# atom-hub-proto-example.net
KiCad netlist of a schematic drawn in EAGLE
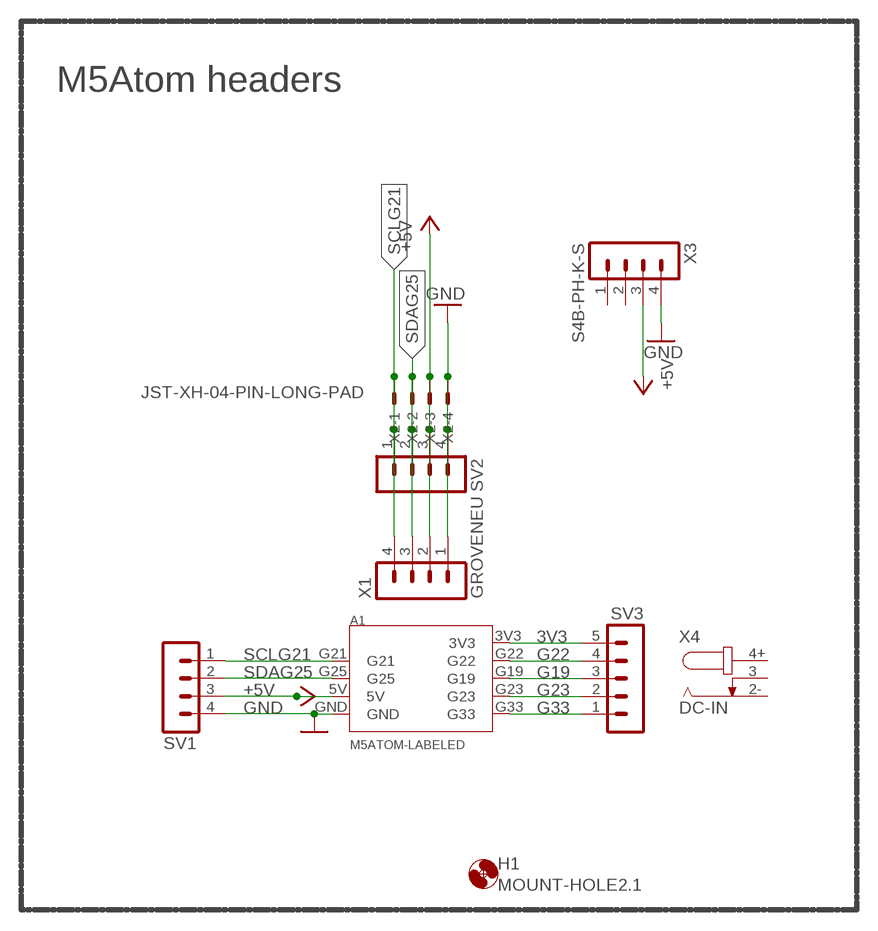
[diagram p0: schematic, sheet 1]

(export (version "E")
  (design (tool "Eeschema 10.0.6"))
  (components
    (comp (ref "A1")
      (value "M5ATOM-LABELED")
      (footprint "eagle-import:M5ATOM-W_-LABELS")
      (libsource (lib "eagle-import") (part "M5ATOM-LABELED"))
    )
    (comp (ref "H1")
      (value "MOUNT-HOLE2.1")
      (footprint "eagle-import:2,1")
      (libsource (lib "eagle-import") (part "MOUNT-HOLE2.1"))
    )
    (comp (ref "SV1")
      (value "MA04-1")
      (footprint "eagle-import:MA04-1")
      (libsource (lib "eagle-import") (part "MA04-1"))
    )
    (comp (ref "SV2")
      (value "MA04-1")
      (footprint "eagle-import:MA04-1")
      (libsource (lib "eagle-import") (part "MA04-1"))
    )
    (comp (ref "SV3")
      (value "MA05-1")
      (footprint "eagle-import:MA05-1")
      (libsource (lib "eagle-import") (part "MA05-1"))
    )
    (comp (ref "X1")
      (value "GROVENEU")
      (footprint "eagle-import:GROVE-NEU")
      (libsource (lib "eagle-import") (part "GROVENEU"))
    )
    (comp (ref "X2")
      (value "JST-XH-04-PIN-LONG-PAD")
      (footprint "eagle-import:JST-XH-04-PACKAGE-LONG-PAD")
      (libsource (lib "eagle-import") (part "JST-XH-04-PIN-LONG-PAD"))
    )
    (comp (ref "X3")
      (value "S4B-PH-K-S")
      (footprint "eagle-import:S4B-PH-K-S")
      (libsource (lib "eagle-import") (part "S4B-PH-K-S"))
    )
    (comp (ref "X4")
      (value "DC-IN")
      (footprint "eagle-import:DC-IN-TH_DC-0440-2.5A-2.0")
      (libsource (lib "eagle-import") (part "DC-IN"))
    )
  )
  (nets
    (net (code "1") (name "+5V") (class "Default")
      (node (ref "A1") (pin "5V") (pinfunction "5V_5V") (pintype "bidirectional"))
      (node (ref "SV1") (pin "3") (pinfunction "3_3") (pintype "passive"))
      (node (ref "SV2") (pin "3") (pinfunction "3_3") (pintype "passive"))
      (node (ref "X1") (pin "2") (pinfunction "2_2") (pintype "passive"))
      (node (ref "X2") (pin "3") (pinfunction "S_3") (pintype "passive"))
      (node (ref "X3") (pin "3") (pinfunction "3_3") (pintype "passive"))
    )
    (net (code "2") (name "/3V3") (class "Default")
      (node (ref "A1") (pin "3V3") (pinfunction "3V3_3V3") (pintype "bidirectional"))
      (node (ref "SV3") (pin "5") (pinfunction "5_5") (pintype "passive"))
    )
    (net (code "3") (name "/G19") (class "Default")
      (node (ref "A1") (pin "G19") (pinfunction "G19_G19") (pintype "bidirectional"))
      (node (ref "SV3") (pin "3") (pinfunction "3_3") (pintype "passive"))
    )
    (net (code "4") (name "/G22") (class "Default")
      (node (ref "A1") (pin "G22") (pinfunction "G22_G22") (pintype "bidirectional"))
      (node (ref "SV3") (pin "4") (pinfunction "4_4") (pintype "passive"))
    )
    (net (code "5") (name "/G23") (class "Default")
      (node (ref "A1") (pin "G23") (pinfunction "G23_G23") (pintype "bidirectional"))
      (node (ref "SV3") (pin "2") (pinfunction "2_2") (pintype "passive"))
    )
    (net (code "6") (name "/G33") (class "Default")
      (node (ref "A1") (pin "G33") (pinfunction "G33_G33") (pintype "bidirectional"))
      (node (ref "SV3") (pin "1") (pinfunction "1_1") (pintype "passive"))
    )
    (net (code "7") (name "GND") (class "Default")
      (node (ref "A1") (pin "GND") (pinfunction "GND_GND") (pintype "bidirectional"))
      (node (ref "SV1") (pin "4") (pinfunction "4_4") (pintype "passive"))
      (node (ref "SV2") (pin "4") (pinfunction "4_4") (pintype "passive"))
      (node (ref "X1") (pin "1") (pinfunction "1_1") (pintype "passive"))
      (node (ref "X2") (pin "4") (pinfunction "S_4") (pintype "passive"))
      (node (ref "X3") (pin "4") (pinfunction "4_4") (pintype "passive"))
    )
    (net (code "8") (name "SCLG21") (class "Default")
      (node (ref "A1") (pin "G21") (pinfunction "G21_G21") (pintype "bidirectional"))
      (node (ref "SV1") (pin "1") (pinfunction "1_1") (pintype "passive"))
      (node (ref "SV2") (pin "1") (pinfunction "1_1") (pintype "passive"))
      (node (ref "X1") (pin "4") (pinfunction "4_4") (pintype "passive"))
      (node (ref "X2") (pin "1") (pinfunction "S_1") (pintype "passive"))
    )
    (net (code "9") (name "SDAG25") (class "Default")
      (node (ref "A1") (pin "G25") (pinfunction "G25_G25") (pintype "bidirectional"))
      (node (ref "SV1") (pin "2") (pinfunction "2_2") (pintype "passive"))
      (node (ref "SV2") (pin "2") (pinfunction "2_2") (pintype "passive"))
      (node (ref "X1") (pin "3") (pinfunction "3_3") (pintype "passive"))
      (node (ref "X2") (pin "2") (pinfunction "S_2") (pintype "passive"))
    )
    (net (code "10") (name "unconnected-(X3-Pad1)") (class "Default")
      (node (ref "X3") (pin "1") (pinfunction "1_1") (pintype "passive"))
    )
    (net (code "11") (name "unconnected-(X3-Pad2)") (class "Default")
      (node (ref "X3") (pin "2") (pinfunction "2_2") (pintype "passive"))
    )
    (net (code "12") (name "unconnected-(X4-1-Pad2-)") (class "Default")
      (node (ref "X4") (pin "2-") (pinfunction "1_2-") (pintype "passive"))
    )
    (net (code "13") (name "unconnected-(X4-2-Pad3)") (class "Default")
      (node (ref "X4") (pin "3") (pinfunction "2_3") (pintype "passive"))
    )
    (net (code "14") (name "unconnected-(X4-3-Pad4+)") (class "Default")
      (node (ref "X4") (pin "4+") (pinfunction "3_4+") (pintype "passive"))
    )
  )
)
